# kijek_d.net
KiCad netlist of a schematic drawn in Altium Designer
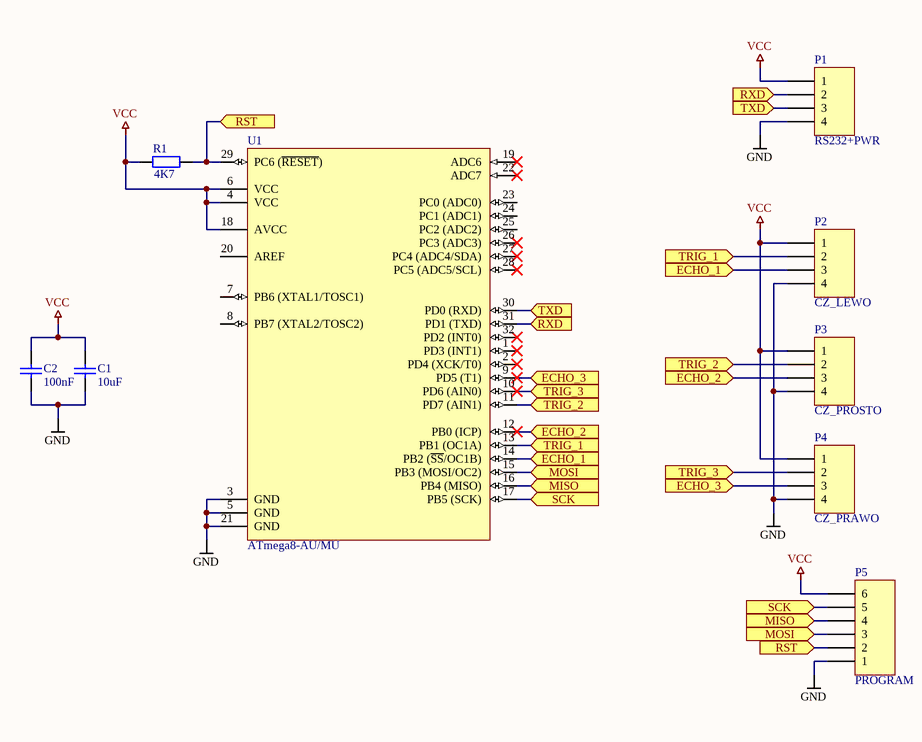
[diagram p0: kijek_d.SchDoc]

(export (version "E")
  (design (tool "Eeschema 10.0.6"))
  (components
    (comp (ref "C1")
      (value "10uF")
      (footprint "C0603")
      (description "Capacitor")
      (libsource (lib "Library") (part "Cap"))
    )
    (comp (ref "C2")
      (value "100nF")
      (footprint "C0402")
      (description "Capacitor")
      (libsource (lib "Library") (part "Cap"))
    )
    (comp (ref "P1")
      (value "RS232+PWR")
      (footprint "MA04-1")
      (description "Header, 4-Pin")
      (libsource (lib "Connectors") (part "Header 4"))
    )
    (comp (ref "P2")
      (value "CZ_LEWO")
      (footprint "MA04-1")
      (description "Header, 4-Pin")
      (libsource (lib "Connectors") (part "Header 4"))
    )
    (comp (ref "P3")
      (value "CZ_PROSTO")
      (footprint "MA04-1")
      (description "Header, 4-Pin")
      (libsource (lib "Connectors") (part "Header 4"))
    )
    (comp (ref "P4")
      (value "CZ_PRAWO")
      (footprint "MA04-1")
      (description "Header, 4-Pin")
      (libsource (lib "Connectors") (part "Header 4"))
    )
    (comp (ref "P5")
      (value "PROGRAM")
      (footprint "SMA06-1")
      (description "Header, 6-Pin")
      (libsource (lib "Connectors") (part "Header 6"))
    )
    (comp (ref "R1")
      (value "4K7")
      (footprint "R0402")
      (description "Resistor")
      (libsource (lib "Library") (part "Res"))
    )
    (comp (ref "U1")
      (value "ATmega8-AU/MU")
      (footprint "TQFP-32A")
      (description "TQFP - 32pin / MLF - 32pin")
      (libsource (lib "IC") (part "ATmega8-AU/MU"))
    )
  )
  (nets
    (net (code "1") (name "/ECHO_1") (class "Default")
      (node (ref "P2") (pin "3") (pinfunction "3_3") (pintype "passive"))
      (node (ref "U1") (pin "14") (pinfunction "PB2_(~{SS}/OC1B)_14") (pintype "bidirectional"))
    )
    (net (code "2") (name "/ECHO_2") (class "Default")
      (node (ref "P3") (pin "3") (pinfunction "3_3") (pintype "passive"))
      (node (ref "U1") (pin "12") (pinfunction "PB0_(ICP)_12") (pintype "bidirectional"))
    )
    (net (code "3") (name "/ECHO_3") (class "Default")
      (node (ref "P4") (pin "3") (pinfunction "3_3") (pintype "passive"))
      (node (ref "U1") (pin "9") (pinfunction "PD5_(T1)_9") (pintype "bidirectional"))
    )
    (net (code "4") (name "/MISO") (class "Default")
      (node (ref "P5") (pin "4") (pinfunction "4_4") (pintype "passive"))
      (node (ref "U1") (pin "16") (pinfunction "PB4_(MISO)_16") (pintype "bidirectional"))
    )
    (net (code "5") (name "/MOSI") (class "Default")
      (node (ref "P5") (pin "3") (pinfunction "3_3") (pintype "passive"))
      (node (ref "U1") (pin "15") (pinfunction "PB3_(MOSI/OC2)_15") (pintype "bidirectional"))
    )
    (net (code "6") (name "/RST") (class "Default")
      (node (ref "P5") (pin "2") (pinfunction "2_2") (pintype "passive"))
      (node (ref "R1") (pin "2") (pinfunction "2_2") (pintype "passive"))
      (node (ref "U1") (pin "29") (pinfunction "PC6_(~{RESET})_29") (pintype "bidirectional"))
    )
    (net (code "7") (name "/RXD") (class "Default")
      (node (ref "P1") (pin "2") (pinfunction "2_2") (pintype "passive"))
      (node (ref "U1") (pin "31") (pinfunction "PD1_(TXD)_31") (pintype "bidirectional"))
    )
    (net (code "8") (name "/SCK") (class "Default")
      (node (ref "P5") (pin "5") (pinfunction "5_5") (pintype "passive"))
      (node (ref "U1") (pin "17") (pinfunction "PB5_(SCK)_17") (pintype "bidirectional"))
    )
    (net (code "9") (name "/TRIG_1") (class "Default")
      (node (ref "P2") (pin "2") (pinfunction "2_2") (pintype "passive"))
      (node (ref "U1") (pin "13") (pinfunction "PB1_(OC1A)_13") (pintype "bidirectional"))
    )
    (net (code "10") (name "/TRIG_2") (class "Default")
      (node (ref "P3") (pin "2") (pinfunction "2_2") (pintype "passive"))
      (node (ref "U1") (pin "11") (pinfunction "PD7_(AIN1)_11") (pintype "bidirectional"))
    )
    (net (code "11") (name "/TRIG_3") (class "Default")
      (node (ref "P4") (pin "2") (pinfunction "2_2") (pintype "passive"))
      (node (ref "U1") (pin "10") (pinfunction "PD6_(AIN0)_10") (pintype "bidirectional"))
    )
    (net (code "12") (name "/TXD") (class "Default")
      (node (ref "P1") (pin "3") (pinfunction "3_3") (pintype "passive"))
      (node (ref "U1") (pin "30") (pinfunction "PD0_(RXD)_30") (pintype "bidirectional"))
    )
    (net (code "13") (name "GND") (class "Default")
      (node (ref "C1") (pin "2") (pinfunction "2_2") (pintype "passive"))
      (node (ref "C2") (pin "2") (pinfunction "2_2") (pintype "passive"))
      (node (ref "P1") (pin "4") (pinfunction "4_4") (pintype "passive"))
      (node (ref "P2") (pin "4") (pinfunction "4_4") (pintype "passive"))
      (node (ref "P3") (pin "4") (pinfunction "4_4") (pintype "passive"))
      (node (ref "P4") (pin "4") (pinfunction "4_4") (pintype "passive"))
      (node (ref "P5") (pin "1") (pinfunction "1_1") (pintype "passive"))
      (node (ref "U1") (pin "21") (pinfunction "GND_21") (pintype "power_in"))
      (node (ref "U1") (pin "3") (pinfunction "GND_3") (pintype "power_in"))
      (node (ref "U1") (pin "5") (pinfunction "GND_5") (pintype "power_in"))
    )
    (net (code "14") (name "VCC") (class "Default")
      (node (ref "C1") (pin "1") (pinfunction "1_1") (pintype "passive"))
      (node (ref "C2") (pin "1") (pinfunction "1_1") (pintype "passive"))
      (node (ref "P1") (pin "1") (pinfunction "1_1") (pintype "passive"))
      (node (ref "P2") (pin "1") (pinfunction "1_1") (pintype "passive"))
      (node (ref "P3") (pin "1") (pinfunction "1_1") (pintype "passive"))
      (node (ref "P4") (pin "1") (pinfunction "1_1") (pintype "passive"))
      (node (ref "P5") (pin "6") (pinfunction "6_6") (pintype "passive"))
      (node (ref "R1") (pin "1") (pinfunction "1_1") (pintype "passive"))
      (node (ref "U1") (pin "18") (pinfunction "AVCC_18") (pintype "power_in"))
      (node (ref "U1") (pin "4") (pinfunction "VCC_4") (pintype "power_in"))
      (node (ref "U1") (pin "6") (pinfunction "VCC_6") (pintype "power_in"))
    )
    (net (code "15") (name "unconnected-(U1-ADC6-Pad19)") (class "Default")
      (node (ref "U1") (pin "19") (pinfunction "ADC6_19") (pintype "input+no_connect"))
    )
    (net (code "16") (name "unconnected-(U1-ADC7-Pad22)") (class "Default")
      (node (ref "U1") (pin "22") (pinfunction "ADC7_22") (pintype "input+no_connect"))
    )
    (net (code "17") (name "unconnected-(U1-AREF-Pad20)") (class "Default")
      (node (ref "U1") (pin "20") (pinfunction "AREF_20") (pintype "passive"))
    )
    (net (code "18") (name "unconnected-(U1-PB6_(XTAL1{slash}TOSC1)-Pad7)") (class "Default")
      (node (ref "U1") (pin "7") (pinfunction "PB6_(XTAL1/TOSC1)_7") (pintype "bidirectional"))
    )
    (net (code "19") (name "unconnected-(U1-PB7_(XTAL2{slash}TOSC2)-Pad8)") (class "Default")
      (node (ref "U1") (pin "8") (pinfunction "PB7_(XTAL2/TOSC2)_8") (pintype "bidirectional"))
    )
    (net (code "20") (name "unconnected-(U1-PC0_(ADC0)-Pad23)") (class "Default")
      (node (ref "U1") (pin "23") (pinfunction "PC0_(ADC0)_23") (pintype "bidirectional"))
    )
    (net (code "21") (name "unconnected-(U1-PC1_(ADC1)-Pad24)") (class "Default")
      (node (ref "U1") (pin "24") (pinfunction "PC1_(ADC1)_24") (pintype "bidirectional"))
    )
    (net (code "22") (name "unconnected-(U1-PC2_(ADC2)-Pad25)") (class "Default")
      (node (ref "U1") (pin "25") (pinfunction "PC2_(ADC2)_25") (pintype "bidirectional"))
    )
    (net (code "23") (name "unconnected-(U1-PC3_(ADC3)-Pad26)") (class "Default")
      (node (ref "U1") (pin "26") (pinfunction "PC3_(ADC3)_26") (pintype "bidirectional+no_connect"))
    )
    (net (code "24") (name "unconnected-(U1-PC4_(ADC4{slash}SDA)-Pad27)") (class "Default")
      (node (ref "U1") (pin "27") (pinfunction "PC4_(ADC4/SDA)_27") (pintype "bidirectional+no_connect"))
    )
    (net (code "25") (name "unconnected-(U1-PC5_(ADC5{slash}SCL)-Pad28)") (class "Default")
      (node (ref "U1") (pin "28") (pinfunction "PC5_(ADC5/SCL)_28") (pintype "bidirectional+no_connect"))
    )
    (net (code "26") (name "unconnected-(U1-PD2_(INT0)-Pad32)") (class "Default")
      (node (ref "U1") (pin "32") (pinfunction "PD2_(INT0)_32") (pintype "bidirectional+no_connect"))
    )
    (net (code "27") (name "unconnected-(U1-PD3_(INT1)-Pad1)") (class "Default")
      (node (ref "U1") (pin "1") (pinfunction "PD3_(INT1)_1") (pintype "bidirectional+no_connect"))
    )
    (net (code "28") (name "unconnected-(U1-PD4_(XCK{slash}T0)-Pad2)") (class "Default")
      (node (ref "U1") (pin "2") (pinfunction "PD4_(XCK/T0)_2") (pintype "bidirectional+no_connect"))
    )
  )
)
